# TobiEncAS5600.net
KiCad netlist of a schematic drawn in EAGLE
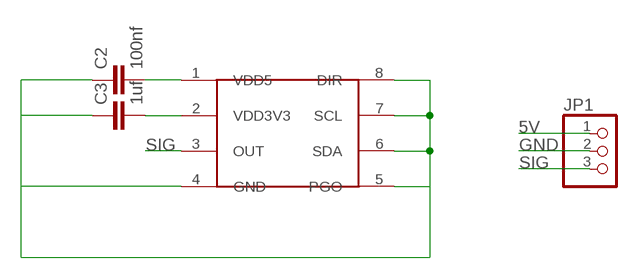
[diagram p0: schematic, sheet 1]

(export (version "E")
  (design (tool "Eeschema 10.0.6"))
  (components
    (comp (ref "C2")
      (value "100nf")
      (footprint "eagle-import:0603-CAP")
      (libsource (lib "eagle-import") (part "CAP0603-CAP"))
    )
    (comp (ref "C3")
      (value "1uf")
      (footprint "eagle-import:0603-CAP")
      (libsource (lib "eagle-import") (part "CAP0603-CAP"))
    )
    (comp (ref "JP1")
      (value "PINHD-1X3")
      (footprint "eagle-import:1X03")
      (libsource (lib "eagle-import") (part "PINHD-1X3"))
    )
    (comp (ref "U$1")
      (value "AS5600")
      (footprint "eagle-import:SO08")
      (libsource (lib "eagle-import") (part "AS5600"))
    )
  )
  (nets
    (net (code "1") (name "/5V") (class "Default")
      (node (ref "C2") (pin "2") (pinfunction "2_2") (pintype "passive"))
      (node (ref "JP1") (pin "1") (pinfunction "1_1") (pintype "passive"))
      (node (ref "U$1") (pin "1") (pinfunction "VDD5_1") (pintype "bidirectional"))
    )
    (net (code "2") (name "/GND") (class "Default")
      (node (ref "C2") (pin "1") (pinfunction "1_1") (pintype "passive"))
      (node (ref "C3") (pin "1") (pinfunction "1_1") (pintype "passive"))
      (node (ref "JP1") (pin "2") (pinfunction "2_2") (pintype "passive"))
      (node (ref "U$1") (pin "4") (pinfunction "GND_4") (pintype "bidirectional"))
      (node (ref "U$1") (pin "5") (pinfunction "PGO_5") (pintype "bidirectional"))
      (node (ref "U$1") (pin "6") (pinfunction "SDA_6") (pintype "bidirectional"))
      (node (ref "U$1") (pin "7") (pinfunction "SCL_7") (pintype "bidirectional"))
      (node (ref "U$1") (pin "8") (pinfunction "DIR_8") (pintype "bidirectional"))
    )
    (net (code "3") (name "/SIG") (class "Default")
      (node (ref "JP1") (pin "3") (pinfunction "3_3") (pintype "passive"))
      (node (ref "U$1") (pin "3") (pinfunction "OUT_3") (pintype "bidirectional"))
    )
    (net (code "4") (name "Net-(U$1-VDD3V3)") (class "Default")
      (node (ref "C3") (pin "2") (pinfunction "2_2") (pintype "passive"))
      (node (ref "U$1") (pin "2") (pinfunction "VDD3V3_2") (pintype "bidirectional"))
    )
  )
)
